# pcb-bldc-servo-3.net
KiCad netlist of a schematic drawn in EAGLE
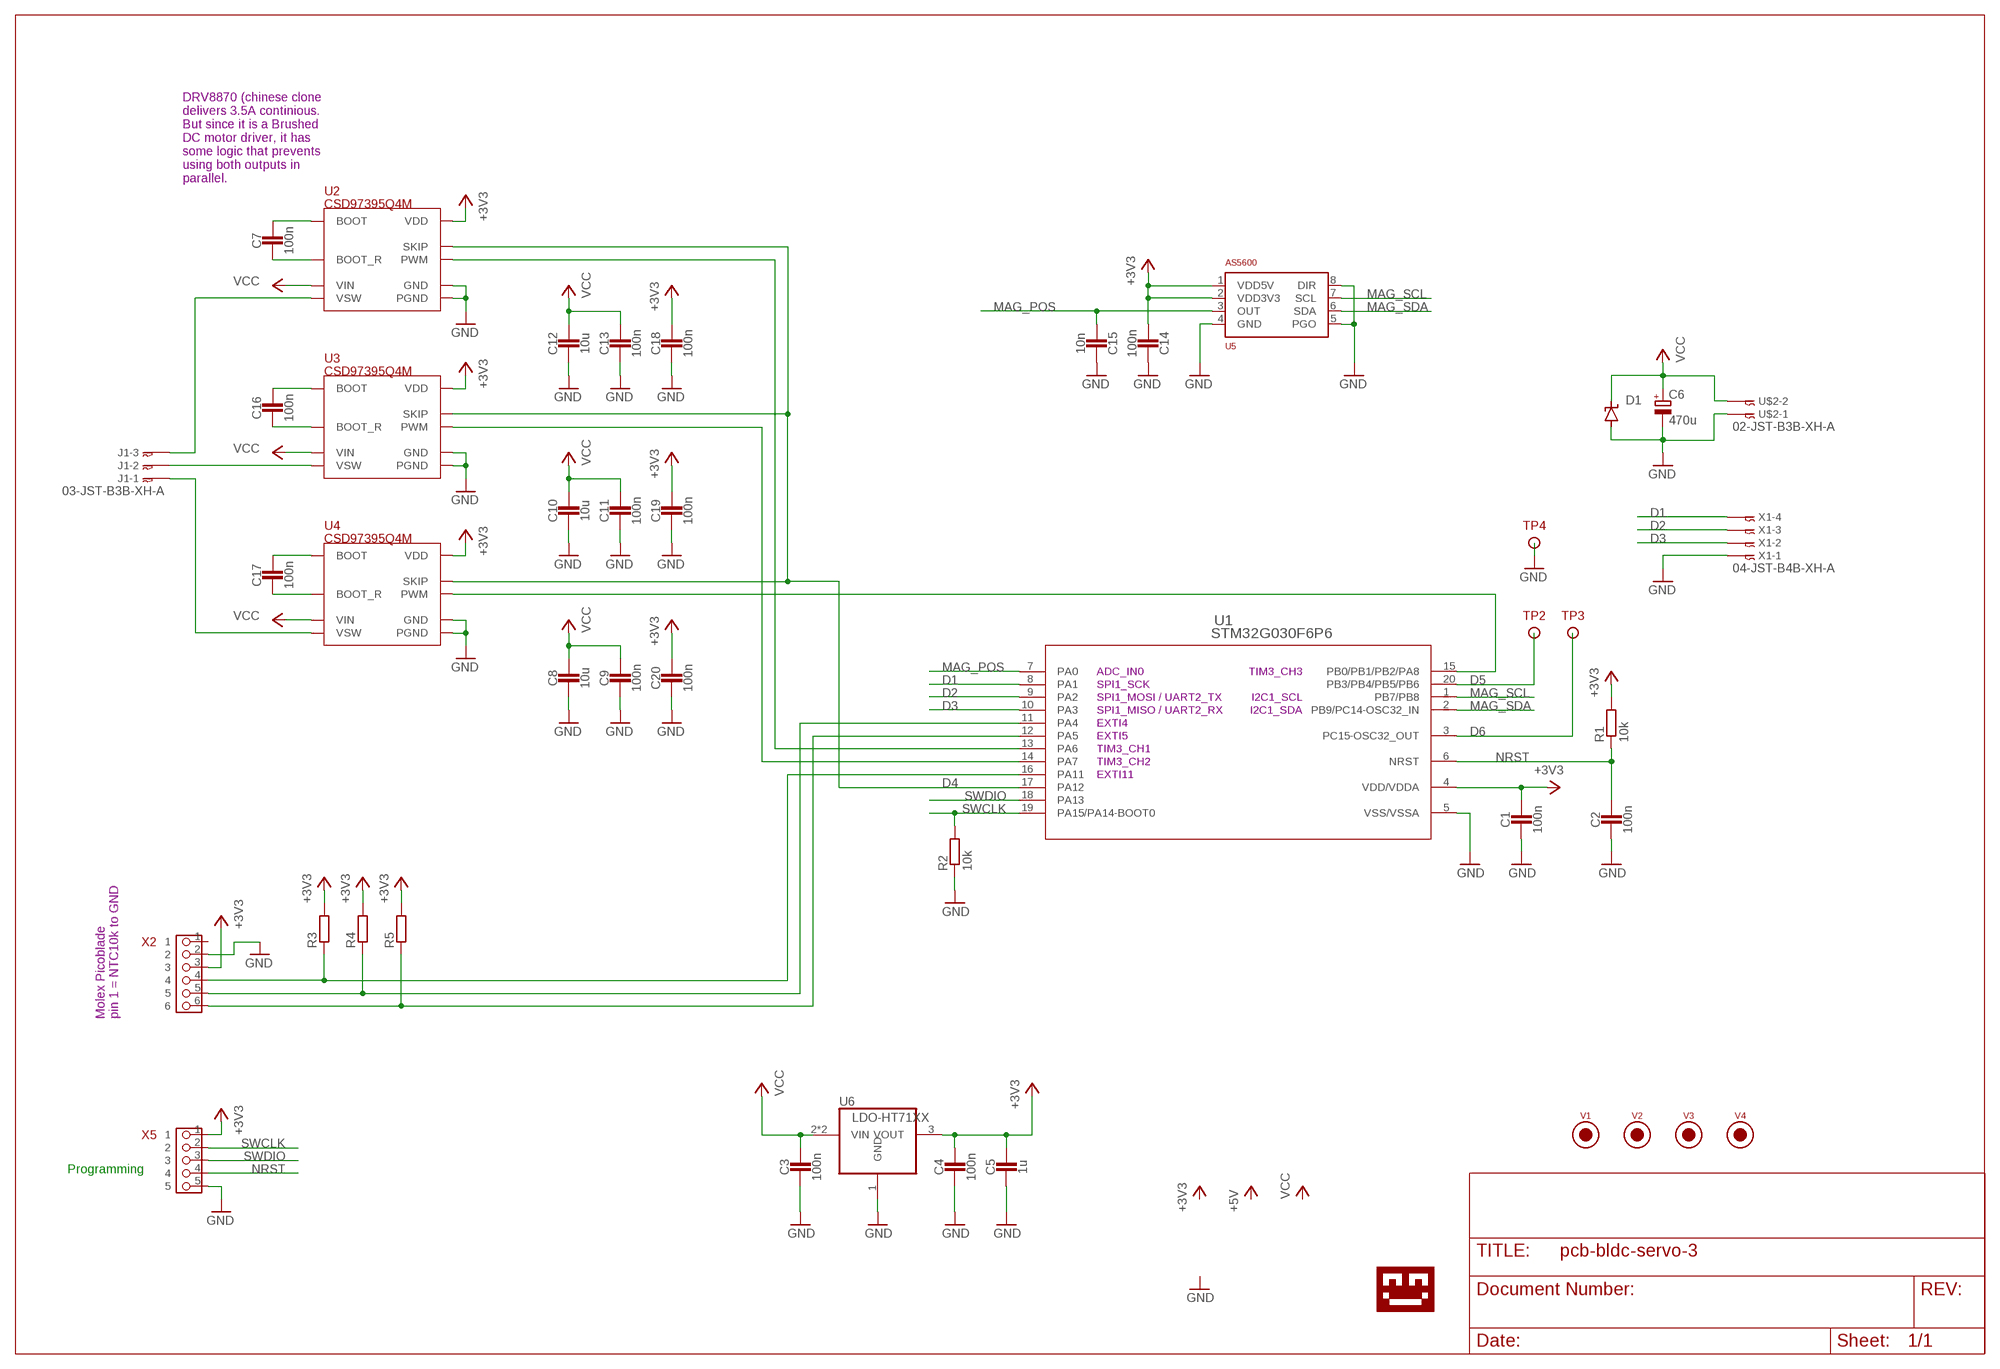
[diagram p0: schematic, sheet 1]

(export (version "E")
  (design (tool "Eeschema 10.0.6"))
  (components
    (comp (ref "C1")
      (value "100n")
      (footprint "eagle-import:0603_CAP")
      (libsource (lib "eagle-import") (part "CAPACITOR0603_CAP"))
    )
    (comp (ref "C2")
      (value "100n")
      (footprint "eagle-import:0603_CAP")
      (libsource (lib "eagle-import") (part "CAPACITOR0603_CAP"))
    )
    (comp (ref "C3")
      (value "100n")
      (footprint "eagle-import:0603_CAP")
      (libsource (lib "eagle-import") (part "CAPACITOR0603_CAP"))
    )
    (comp (ref "C4")
      (value "100n")
      (footprint "eagle-import:0603_CAP")
      (libsource (lib "eagle-import") (part "CAPACITOR0603_CAP"))
    )
    (comp (ref "C5")
      (value "1u")
      (footprint "eagle-import:0603_CAP")
      (libsource (lib "eagle-import") (part "CAPACITOR0603_CAP"))
    )
    (comp (ref "C6")
      (value "470u")
      (footprint "eagle-import:153CLV-1010")
      (libsource (lib "eagle-import") (part "CPOL-EU153CLV-1010"))
    )
    (comp (ref "C7")
      (value "100n")
      (footprint "eagle-import:0603_CAP")
      (libsource (lib "eagle-import") (part "CAPACITOR0603_CAP"))
    )
    (comp (ref "C8")
      (value "10u")
      (footprint "eagle-import:1206_CAP")
      (libsource (lib "eagle-import") (part "CAPACITOR1206_CAP"))
    )
    (comp (ref "C9")
      (value "100n")
      (footprint "eagle-import:0603_CAP")
      (libsource (lib "eagle-import") (part "CAPACITOR0603_CAP"))
    )
    (comp (ref "C10")
      (value "10u")
      (footprint "eagle-import:1206_CAP")
      (libsource (lib "eagle-import") (part "CAPACITOR1206_CAP"))
    )
    (comp (ref "C11")
      (value "100n")
      (footprint "eagle-import:0603_CAP")
      (libsource (lib "eagle-import") (part "CAPACITOR0603_CAP"))
    )
    (comp (ref "C12")
      (value "10u")
      (footprint "eagle-import:1206_CAP")
      (libsource (lib "eagle-import") (part "CAPACITOR1206_CAP"))
    )
    (comp (ref "C13")
      (value "100n")
      (footprint "eagle-import:0603_CAP")
      (libsource (lib "eagle-import") (part "CAPACITOR0603_CAP"))
    )
    (comp (ref "C14")
      (value "100n")
      (footprint "eagle-import:0603_CAP")
      (libsource (lib "eagle-import") (part "CAPACITOR0603_CAP"))
    )
    (comp (ref "C15")
      (value "10n")
      (footprint "eagle-import:0603_CAP")
      (libsource (lib "eagle-import") (part "CAPACITOR0603_CAP"))
    )
    (comp (ref "C16")
      (value "100n")
      (footprint "eagle-import:0603_CAP")
      (libsource (lib "eagle-import") (part "CAPACITOR0603_CAP"))
    )
    (comp (ref "C17")
      (value "100n")
      (footprint "eagle-import:0603_CAP")
      (libsource (lib "eagle-import") (part "CAPACITOR0603_CAP"))
    )
    (comp (ref "C18")
      (value "100n")
      (footprint "eagle-import:0603_CAP")
      (libsource (lib "eagle-import") (part "CAPACITOR0603_CAP"))
    )
    (comp (ref "C19")
      (value "100n")
      (footprint "eagle-import:0603_CAP")
      (libsource (lib "eagle-import") (part "CAPACITOR0603_CAP"))
    )
    (comp (ref "C20")
      (value "100n")
      (footprint "eagle-import:0603_CAP")
      (libsource (lib "eagle-import") (part "CAPACITOR0603_CAP"))
    )
    (comp (ref "D1")
      (value "SUPPRESSOR-SMBJ")
      (footprint "eagle-import:SMBJ")
      (libsource (lib "eagle-import") (part "SUPPRESSOR-SMBJ"))
    )
    (comp (ref "J1")
      (value "03-JST-B3B-XH-A")
      (footprint "eagle-import:B3B-XH")
      (libsource (lib "eagle-import") (part "03-JST-B3B-XH-A"))
    )
    (comp (ref "R1")
      (value "10k")
      (footprint "eagle-import:0603-RES")
      (libsource (lib "eagle-import") (part "RESISTOR0603_RES"))
    )
    (comp (ref "R2")
      (value "10k")
      (footprint "eagle-import:0603-RES")
      (libsource (lib "eagle-import") (part "RESISTOR0603_RES"))
    )
    (comp (ref "R3")
      (value "RESISTOR0603_RES")
      (footprint "eagle-import:0603-RES")
      (libsource (lib "eagle-import") (part "RESISTOR0603_RES"))
    )
    (comp (ref "R4")
      (value "RESISTOR0603_RES")
      (footprint "eagle-import:0603-RES")
      (libsource (lib "eagle-import") (part "RESISTOR0603_RES"))
    )
    (comp (ref "R5")
      (value "RESISTOR0603_RES")
      (footprint "eagle-import:0603-RES")
      (libsource (lib "eagle-import") (part "RESISTOR0603_RES"))
    )
    (comp (ref "TP2")
      (value "TESTPIN1MM")
      (footprint "eagle-import:PIN-SMD-1X1-TEST_1M0")
      (libsource (lib "eagle-import") (part "TESTPIN1MM"))
    )
    (comp (ref "TP3")
      (value "TESTPIN1MM")
      (footprint "eagle-import:PIN-SMD-1X1-TEST_1M0")
      (libsource (lib "eagle-import") (part "TESTPIN1MM"))
    )
    (comp (ref "TP4")
      (value "TESTPIN1MM")
      (footprint "eagle-import:PIN-SMD-1X1-TEST_1M0")
      (libsource (lib "eagle-import") (part "TESTPIN1MM"))
    )
    (comp (ref "U$1")
      (value "LOGO-TOBENG-1MM-FINISH")
      (footprint "eagle-import:TOBENG-1MM-FINISH")
      (libsource (lib "eagle-import") (part "LOGO-TOBENG-1MM-FINISH"))
    )
    (comp (ref "U$2")
      (value "02-JST-B3B-XH-A")
      (footprint "eagle-import:B2B-XH")
      (libsource (lib "eagle-import") (part "02-JST-B3B-XH-A"))
    )
    (comp (ref "U1")
      (value "STM32G030F6P6")
      (footprint "eagle-import:TSSOP20")
      (fields (field (name "COPYRIGHT") "Copyright (C) 2024 Ultra Librarian. All rights reserved."))
      (libsource (lib "eagle-import") (part "STM32G030F6P6"))
    )
    (comp (ref "U2")
      (value "CSD97395Q4M")
      (footprint "eagle-import:CSD97395Q4M")
      (libsource (lib "eagle-import") (part "CSD97395Q4M"))
    )
    (comp (ref "U3")
      (value "CSD97395Q4M")
      (footprint "eagle-import:CSD97395Q4M")
      (libsource (lib "eagle-import") (part "CSD97395Q4M"))
    )
    (comp (ref "U4")
      (value "CSD97395Q4M")
      (footprint "eagle-import:CSD97395Q4M")
      (libsource (lib "eagle-import") (part "CSD97395Q4M"))
    )
    (comp (ref "U5")
      (value "AS5600")
      (footprint "eagle-import:SOIC-8")
      (libsource (lib "eagle-import") (part "AS5600"))
    )
    (comp (ref "U6")
      (value "LDO-HT71XX")
      (footprint "eagle-import:SOT-89")
      (libsource (lib "eagle-import") (part "LDO-HT71XX"))
    )
    (comp (ref "V1")
      (value "FIDUCIAL2MM")
      (footprint "eagle-import:FIDUCIAL_2MM")
      (libsource (lib "eagle-import") (part "FIDUCIAL2MM"))
    )
    (comp (ref "V2")
      (value "FIDUCIAL2MM")
      (footprint "eagle-import:FIDUCIAL_2MM")
      (libsource (lib "eagle-import") (part "FIDUCIAL2MM"))
    )
    (comp (ref "V3")
      (value "FIDUCIAL2MM")
      (footprint "eagle-import:FIDUCIAL_2MM")
      (libsource (lib "eagle-import") (part "FIDUCIAL2MM"))
    )
    (comp (ref "V4")
      (value "FIDUCIAL2MM")
      (footprint "eagle-import:FIDUCIAL_2MM")
      (libsource (lib "eagle-import") (part "FIDUCIAL2MM"))
    )
    (comp (ref "X1")
      (value "04-JST-B4B-XH-A")
      (footprint "eagle-import:B4B-XH")
      (libsource (lib "eagle-import") (part "04-JST-B4B-XH-A"))
    )
    (comp (ref "X2")
      (value "PIN_6X1")
      (footprint "eagle-import:PIN_6X1_MOLEX_PICOBLADE")
      (libsource (lib "eagle-import") (part "PIN_6X1"))
    )
    (comp (ref "X5")
      (value "PIN_5X1HD")
      (footprint "eagle-import:PIN_5X1_HD")
      (libsource (lib "eagle-import") (part "PIN_5X1HD"))
    )
  )
  (nets
    (net (code "1") (name "+3V3") (class "Default")
      (node (ref "C1") (pin "1") (pinfunction "1_1") (pintype "bidirectional"))
      (node (ref "C14") (pin "1") (pinfunction "1_1") (pintype "bidirectional"))
      (node (ref "C18") (pin "1") (pinfunction "1_1") (pintype "bidirectional"))
      (node (ref "C19") (pin "1") (pinfunction "1_1") (pintype "bidirectional"))
      (node (ref "C20") (pin "1") (pinfunction "1_1") (pintype "bidirectional"))
      (node (ref "C4") (pin "1") (pinfunction "1_1") (pintype "bidirectional"))
      (node (ref "C5") (pin "1") (pinfunction "1_1") (pintype "bidirectional"))
      (node (ref "R1") (pin "2") (pinfunction "2_2") (pintype "passive"))
      (node (ref "R3") (pin "2") (pinfunction "2_2") (pintype "passive"))
      (node (ref "R4") (pin "2") (pinfunction "2_2") (pintype "passive"))
      (node (ref "R5") (pin "2") (pinfunction "2_2") (pintype "passive"))
      (node (ref "U1") (pin "4") (pinfunction "VDD/VDDA_4") (pintype "power_in"))
      (node (ref "U2") (pin "VDD") (pinfunction "VDD_VDD") (pintype "bidirectional"))
      (node (ref "U2") (pin "VDD1") (pinfunction "VDD_VDD1") (pintype "bidirectional"))
      (node (ref "U3") (pin "VDD") (pinfunction "VDD_VDD") (pintype "bidirectional"))
      (node (ref "U3") (pin "VDD1") (pinfunction "VDD_VDD1") (pintype "bidirectional"))
      (node (ref "U4") (pin "VDD") (pinfunction "VDD_VDD") (pintype "bidirectional"))
      (node (ref "U4") (pin "VDD1") (pinfunction "VDD_VDD1") (pintype "bidirectional"))
      (node (ref "U5") (pin "1") (pinfunction "VDD5V_1") (pintype "bidirectional"))
      (node (ref "U5") (pin "2") (pinfunction "VDD3V3_2") (pintype "bidirectional"))
      (node (ref "U6") (pin "3") (pinfunction "VOUT_3") (pintype "output"))
      (node (ref "X2") (pin "3") (pinfunction "3_3") (pintype "bidirectional"))
      (node (ref "X5") (pin "1") (pinfunction "1_1") (pintype "bidirectional"))
    )
    (net (code "3") (name "/D1") (class "Default")
      (node (ref "U1") (pin "8") (pinfunction "PA1_8") (pintype "bidirectional"))
      (node (ref "X1") (pin "P$4") (pinfunction "1_P$4") (pintype "passive"))
    )
    (net (code "4") (name "/D2") (class "Default")
      (node (ref "U1") (pin "9") (pinfunction "PA2_9") (pintype "bidirectional"))
      (node (ref "X1") (pin "P$3") (pinfunction "1_P$3") (pintype "passive"))
    )
    (net (code "5") (name "/D3") (class "Default")
      (node (ref "U1") (pin "10") (pinfunction "PA3_10") (pintype "bidirectional"))
      (node (ref "X1") (pin "P$2") (pinfunction "1_P$2") (pintype "passive"))
    )
    (net (code "6") (name "/D4") (class "Default")
      (node (ref "U1") (pin "17") (pinfunction "PA12_17") (pintype "bidirectional"))
      (node (ref "U2") (pin "SKIP") (pinfunction "SKIP_SKIP") (pintype "bidirectional"))
      (node (ref "U2") (pin "SKIP1") (pinfunction "SKIP_SKIP1") (pintype "bidirectional"))
      (node (ref "U3") (pin "SKIP") (pinfunction "SKIP_SKIP") (pintype "bidirectional"))
      (node (ref "U3") (pin "SKIP1") (pinfunction "SKIP_SKIP1") (pintype "bidirectional"))
      (node (ref "U4") (pin "SKIP") (pinfunction "SKIP_SKIP") (pintype "bidirectional"))
      (node (ref "U4") (pin "SKIP1") (pinfunction "SKIP_SKIP1") (pintype "bidirectional"))
    )
    (net (code "7") (name "/D5") (class "Default")
      (node (ref "TP2") (pin "1") (pinfunction "1_1") (pintype "bidirectional"))
      (node (ref "U1") (pin "20") (pinfunction "PB3/PB4/PB5/PB6_20") (pintype "bidirectional"))
    )
    (net (code "8") (name "/D6") (class "Default")
      (node (ref "TP3") (pin "1") (pinfunction "1_1") (pintype "bidirectional"))
      (node (ref "U1") (pin "3") (pinfunction "PC15-OSC32_OUT_3") (pintype "bidirectional"))
    )
    (net (code "9") (name "/MAG_POS") (class "Default")
      (node (ref "C15") (pin "1") (pinfunction "1_1") (pintype "bidirectional"))
      (node (ref "U1") (pin "7") (pinfunction "PA0_7") (pintype "bidirectional"))
      (node (ref "U5") (pin "3") (pinfunction "OUT_3") (pintype "bidirectional"))
    )
    (net (code "10") (name "/MAG_SCL") (class "Default")
      (node (ref "U1") (pin "1") (pinfunction "PB7/PB8_1") (pintype "bidirectional"))
      (node (ref "U5") (pin "7") (pinfunction "SCL_7") (pintype "bidirectional"))
    )
    (net (code "11") (name "/MAG_SDA") (class "Default")
      (node (ref "U1") (pin "2") (pinfunction "PB9/PC14-OSC32_IN_2") (pintype "bidirectional"))
      (node (ref "U5") (pin "6") (pinfunction "SDA_6") (pintype "bidirectional"))
    )
    (net (code "12") (name "/NRST") (class "Default")
      (node (ref "C2") (pin "1") (pinfunction "1_1") (pintype "bidirectional"))
      (node (ref "R1") (pin "1") (pinfunction "1_1") (pintype "passive"))
      (node (ref "U1") (pin "6") (pinfunction "NRST_6") (pintype "bidirectional"))
      (node (ref "X5") (pin "4") (pinfunction "4_4") (pintype "bidirectional"))
    )
    (net (code "13") (name "/SWCLK") (class "Default")
      (node (ref "R2") (pin "2") (pinfunction "2_2") (pintype "passive"))
      (node (ref "U1") (pin "19") (pinfunction "PA15/PA14-BOOT0_19") (pintype "bidirectional"))
      (node (ref "X5") (pin "2") (pinfunction "2_2") (pintype "bidirectional"))
    )
    (net (code "14") (name "/SWDIO") (class "Default")
      (node (ref "U1") (pin "18") (pinfunction "PA13_18") (pintype "bidirectional"))
      (node (ref "X5") (pin "3") (pinfunction "3_3") (pintype "bidirectional"))
    )
    (net (code "15") (name "GND") (class "Default")
      (node (ref "C1") (pin "2") (pinfunction "2_2") (pintype "bidirectional"))
      (node (ref "C10") (pin "2") (pinfunction "2_2") (pintype "bidirectional"))
      (node (ref "C11") (pin "2") (pinfunction "2_2") (pintype "bidirectional"))
      (node (ref "C12") (pin "2") (pinfunction "2_2") (pintype "bidirectional"))
      (node (ref "C13") (pin "2") (pinfunction "2_2") (pintype "bidirectional"))
      (node (ref "C14") (pin "2") (pinfunction "2_2") (pintype "bidirectional"))
      (node (ref "C15") (pin "2") (pinfunction "2_2") (pintype "bidirectional"))
      (node (ref "C18") (pin "2") (pinfunction "2_2") (pintype "bidirectional"))
      (node (ref "C19") (pin "2") (pinfunction "2_2") (pintype "bidirectional"))
      (node (ref "C2") (pin "2") (pinfunction "2_2") (pintype "bidirectional"))
      (node (ref "C20") (pin "2") (pinfunction "2_2") (pintype "bidirectional"))
      (node (ref "C3") (pin "2") (pinfunction "2_2") (pintype "bidirectional"))
      (node (ref "C4") (pin "2") (pinfunction "2_2") (pintype "bidirectional"))
      (node (ref "C5") (pin "2") (pinfunction "2_2") (pintype "bidirectional"))
      (node (ref "C6") (pin "-") (pinfunction "-_-") (pintype "passive"))
      (node (ref "C8") (pin "2") (pinfunction "2_2") (pintype "bidirectional"))
      (node (ref "C9") (pin "2") (pinfunction "2_2") (pintype "bidirectional"))
      (node (ref "D1") (pin "A") (pinfunction "A_A") (pintype "passive"))
      (node (ref "R2") (pin "1") (pinfunction "1_1") (pintype "passive"))
      (node (ref "TP4") (pin "1") (pinfunction "1_1") (pintype "bidirectional"))
      (node (ref "U$2") (pin "P$1") (pinfunction "1_P$1") (pintype "passive"))
      (node (ref "U1") (pin "5") (pinfunction "VSS/VSSA_5") (pintype "power_in"))
      (node (ref "U2") (pin "GND") (pinfunction "GND_GND") (pintype "bidirectional"))
      (node (ref "U2") (pin "GND1") (pinfunction "GND_GND1") (pintype "bidirectional"))
      (node (ref "U2") (pin "PGND") (pinfunction "PGND_PGND") (pintype "bidirectional"))
      (node (ref "U3") (pin "GND") (pinfunction "GND_GND") (pintype "bidirectional"))
      (node (ref "U3") (pin "GND1") (pinfunction "GND_GND1") (pintype "bidirectional"))
      (node (ref "U3") (pin "PGND") (pinfunction "PGND_PGND") (pintype "bidirectional"))
      (node (ref "U4") (pin "GND") (pinfunction "GND_GND") (pintype "bidirectional"))
      (node (ref "U4") (pin "GND1") (pinfunction "GND_GND1") (pintype "bidirectional"))
      (node (ref "U4") (pin "PGND") (pinfunction "PGND_PGND") (pintype "bidirectional"))
      (node (ref "U5") (pin "4") (pinfunction "GND_4") (pintype "bidirectional"))
      (node (ref "U5") (pin "5") (pinfunction "PGO_5") (pintype "bidirectional"))
      (node (ref "U5") (pin "8") (pinfunction "DIR_8") (pintype "bidirectional"))
      (node (ref "U6") (pin "1") (pinfunction "GND_1") (pintype "power_in"))
      (node (ref "X1") (pin "P$1") (pinfunction "1_P$1") (pintype "passive"))
      (node (ref "X2") (pin "2") (pinfunction "2_2") (pintype "bidirectional"))
      (node (ref "X5") (pin "5") (pinfunction "5_5") (pintype "bidirectional"))
    )
    (net (code "16") (name "Net-(C7-Pad1)") (class "Default")
      (node (ref "C7") (pin "1") (pinfunction "1_1") (pintype "bidirectional"))
      (node (ref "U2") (pin "BOOT") (pinfunction "BOOT_BOOT") (pintype "bidirectional"))
      (node (ref "U2") (pin "BOOT1") (pinfunction "BOOT_BOOT1") (pintype "bidirectional"))
    )
    (net (code "17") (name "Net-(C7-Pad2)") (class "Default")
      (node (ref "C7") (pin "2") (pinfunction "2_2") (pintype "bidirectional"))
      (node (ref "U2") (pin "BOOT_R") (pinfunction "BOOT_R_BOOT_R") (pintype "bidirectional"))
      (node (ref "U2") (pin "BOOT_R1") (pinfunction "BOOT_R_BOOT_R1") (pintype "bidirectional"))
    )
    (net (code "18") (name "Net-(C16-Pad1)") (class "Default")
      (node (ref "C16") (pin "1") (pinfunction "1_1") (pintype "bidirectional"))
      (node (ref "U3") (pin "BOOT") (pinfunction "BOOT_BOOT") (pintype "bidirectional"))
      (node (ref "U3") (pin "BOOT1") (pinfunction "BOOT_BOOT1") (pintype "bidirectional"))
    )
    (net (code "19") (name "Net-(C16-Pad2)") (class "Default")
      (node (ref "C16") (pin "2") (pinfunction "2_2") (pintype "bidirectional"))
      (node (ref "U3") (pin "BOOT_R") (pinfunction "BOOT_R_BOOT_R") (pintype "bidirectional"))
      (node (ref "U3") (pin "BOOT_R1") (pinfunction "BOOT_R_BOOT_R1") (pintype "bidirectional"))
    )
    (net (code "20") (name "Net-(C17-Pad1)") (class "Default")
      (node (ref "C17") (pin "1") (pinfunction "1_1") (pintype "bidirectional"))
      (node (ref "U4") (pin "BOOT") (pinfunction "BOOT_BOOT") (pintype "bidirectional"))
      (node (ref "U4") (pin "BOOT1") (pinfunction "BOOT_BOOT1") (pintype "bidirectional"))
    )
    (net (code "21") (name "Net-(C17-Pad2)") (class "Default")
      (node (ref "C17") (pin "2") (pinfunction "2_2") (pintype "bidirectional"))
      (node (ref "U4") (pin "BOOT_R") (pinfunction "BOOT_R_BOOT_R") (pintype "bidirectional"))
      (node (ref "U4") (pin "BOOT_R1") (pinfunction "BOOT_R_BOOT_R1") (pintype "bidirectional"))
    )
    (net (code "22") (name "Net-(J1A-1)") (class "Default")
      (node (ref "J1") (pin "P$1") (pinfunction "1_P$1") (pintype "passive"))
      (node (ref "U4") (pin "VSW") (pinfunction "VSW_VSW") (pintype "bidirectional"))
      (node (ref "U4") (pin "VSW1") (pinfunction "VSW_VSW1") (pintype "bidirectional"))
      (node (ref "U4") (pin "VSW2") (pinfunction "VSW_VSW2") (pintype "bidirectional"))
      (node (ref "U4") (pin "VSW3") (pinfunction "VSW_VSW3") (pintype "bidirectional"))
      (node (ref "U4") (pin "VSW4") (pinfunction "VSW_VSW4") (pintype "bidirectional"))
      (node (ref "U4") (pin "VSW5") (pinfunction "VSW_VSW5") (pintype "bidirectional"))
      (node (ref "U4") (pin "VSW6") (pinfunction "VSW_VSW6") (pintype "bidirectional"))
    )
    (net (code "23") (name "Net-(J1B-1)") (class "Default")
      (node (ref "J1") (pin "P$2") (pinfunction "1_P$2") (pintype "passive"))
      (node (ref "U3") (pin "VSW") (pinfunction "VSW_VSW") (pintype "bidirectional"))
      (node (ref "U3") (pin "VSW1") (pinfunction "VSW_VSW1") (pintype "bidirectional"))
      (node (ref "U3") (pin "VSW2") (pinfunction "VSW_VSW2") (pintype "bidirectional"))
      (node (ref "U3") (pin "VSW3") (pinfunction "VSW_VSW3") (pintype "bidirectional"))
      (node (ref "U3") (pin "VSW4") (pinfunction "VSW_VSW4") (pintype "bidirectional"))
      (node (ref "U3") (pin "VSW5") (pinfunction "VSW_VSW5") (pintype "bidirectional"))
      (node (ref "U3") (pin "VSW6") (pinfunction "VSW_VSW6") (pintype "bidirectional"))
    )
    (net (code "24") (name "Net-(J1C-1)") (class "Default")
      (node (ref "J1") (pin "P$3") (pinfunction "1_P$3") (pintype "passive"))
      (node (ref "U2") (pin "VSW") (pinfunction "VSW_VSW") (pintype "bidirectional"))
      (node (ref "U2") (pin "VSW1") (pinfunction "VSW_VSW1") (pintype "bidirectional"))
      (node (ref "U2") (pin "VSW2") (pinfunction "VSW_VSW2") (pintype "bidirectional"))
      (node (ref "U2") (pin "VSW3") (pinfunction "VSW_VSW3") (pintype "bidirectional"))
      (node (ref "U2") (pin "VSW4") (pinfunction "VSW_VSW4") (pintype "bidirectional"))
      (node (ref "U2") (pin "VSW5") (pinfunction "VSW_VSW5") (pintype "bidirectional"))
      (node (ref "U2") (pin "VSW6") (pinfunction "VSW_VSW6") (pintype "bidirectional"))
    )
    (net (code "25") (name "Net-(U1-PA4)") (class "Default")
      (node (ref "R4") (pin "1") (pinfunction "1_1") (pintype "passive"))
      (node (ref "U1") (pin "11") (pinfunction "PA4_11") (pintype "bidirectional"))
      (node (ref "X2") (pin "5") (pinfunction "5_5") (pintype "bidirectional"))
    )
    (net (code "26") (name "Net-(U1-PA5)") (class "Default")
      (node (ref "R5") (pin "1") (pinfunction "1_1") (pintype "passive"))
      (node (ref "U1") (pin "12") (pinfunction "PA5_12") (pintype "bidirectional"))
      (node (ref "X2") (pin "6") (pinfunction "6_6") (pintype "bidirectional"))
    )
    (net (code "27") (name "Net-(U1-PA6)") (class "Default")
      (node (ref "U1") (pin "13") (pinfunction "PA6_13") (pintype "bidirectional"))
      (node (ref "U2") (pin "PWM") (pinfunction "PWM_PWM") (pintype "bidirectional"))
      (node (ref "U2") (pin "PWM1") (pinfunction "PWM_PWM1") (pintype "bidirectional"))
    )
    (net (code "28") (name "Net-(U1-PA7)") (class "Default")
      (node (ref "U1") (pin "14") (pinfunction "PA7_14") (pintype "bidirectional"))
      (node (ref "U3") (pin "PWM") (pinfunction "PWM_PWM") (pintype "bidirectional"))
      (node (ref "U3") (pin "PWM1") (pinfunction "PWM_PWM1") (pintype "bidirectional"))
    )
    (net (code "29") (name "Net-(U1-PA11)") (class "Default")
      (node (ref "R3") (pin "1") (pinfunction "1_1") (pintype "passive"))
      (node (ref "U1") (pin "16") (pinfunction "PA11_16") (pintype "bidirectional"))
      (node (ref "X2") (pin "4") (pinfunction "4_4") (pintype "bidirectional"))
    )
    (net (code "30") (name "Net-(U1-PB0{slash}PB1{slash}PB2{slash}PA8)") (class "Default")
      (node (ref "U1") (pin "15") (pinfunction "PB0/PB1/PB2/PA8_15") (pintype "bidirectional"))
      (node (ref "U4") (pin "PWM") (pinfunction "PWM_PWM") (pintype "bidirectional"))
      (node (ref "U4") (pin "PWM1") (pinfunction "PWM_PWM1") (pintype "bidirectional"))
    )
    (net (code "31") (name "VCC") (class "Default")
      (node (ref "C10") (pin "1") (pinfunction "1_1") (pintype "bidirectional"))
      (node (ref "C11") (pin "1") (pinfunction "1_1") (pintype "bidirectional"))
      (node (ref "C12") (pin "1") (pinfunction "1_1") (pintype "bidirectional"))
      (node (ref "C13") (pin "1") (pinfunction "1_1") (pintype "bidirectional"))
      (node (ref "C3") (pin "1") (pinfunction "1_1") (pintype "bidirectional"))
      (node (ref "C6") (pin "+") (pinfunction "+_+") (pintype "passive"))
      (node (ref "C8") (pin "1") (pinfunction "1_1") (pintype "bidirectional"))
      (node (ref "C9") (pin "1") (pinfunction "1_1") (pintype "bidirectional"))
      (node (ref "D1") (pin "C") (pinfunction "C_C") (pintype "passive"))
      (node (ref "U$2") (pin "P$2") (pinfunction "1_P$2") (pintype "passive"))
      (node (ref "U2") (pin "VIN") (pinfunction "VIN_VIN") (pintype "bidirectional"))
      (node (ref "U2") (pin "VIN1") (pinfunction "VIN_VIN1") (pintype "bidirectional"))
      (node (ref "U2") (pin "VIN2") (pinfunction "VIN_VIN2") (pintype "bidirectional"))
      (node (ref "U2") (pin "VIN3") (pinfunction "VIN_VIN3") (pintype "bidirectional"))
      (node (ref "U2") (pin "VIN4") (pinfunction "VIN_VIN4") (pintype "bidirectional"))
      (node (ref "U2") (pin "VIN5") (pinfunction "VIN_VIN5") (pintype "bidirectional"))
      (node (ref "U2") (pin "VIN6") (pinfunction "VIN_VIN6") (pintype "bidirectional"))
      (node (ref "U3") (pin "VIN") (pinfunction "VIN_VIN") (pintype "bidirectional"))
      (node (ref "U3") (pin "VIN1") (pinfunction "VIN_VIN1") (pintype "bidirectional"))
      (node (ref "U3") (pin "VIN2") (pinfunction "VIN_VIN2") (pintype "bidirectional"))
      (node (ref "U3") (pin "VIN3") (pinfunction "VIN_VIN3") (pintype "bidirectional"))
      (node (ref "U3") (pin "VIN4") (pinfunction "VIN_VIN4") (pintype "bidirectional"))
      (node (ref "U3") (pin "VIN5") (pinfunction "VIN_VIN5") (pintype "bidirectional"))
      (node (ref "U3") (pin "VIN6") (pinfunction "VIN_VIN6") (pintype "bidirectional"))
      (node (ref "U4") (pin "VIN") (pinfunction "VIN_VIN") (pintype "bidirectional"))
      (node (ref "U4") (pin "VIN1") (pinfunction "VIN_VIN1") (pintype "bidirectional"))
      (node (ref "U4") (pin "VIN2") (pinfunction "VIN_VIN2") (pintype "bidirectional"))
      (node (ref "U4") (pin "VIN3") (pinfunction "VIN_VIN3") (pintype "bidirectional"))
      (node (ref "U4") (pin "VIN4") (pinfunction "VIN_VIN4") (pintype "bidirectional"))
      (node (ref "U4") (pin "VIN5") (pinfunction "VIN_VIN5") (pintype "bidirectional"))
      (node (ref "U4") (pin "VIN6") (pinfunction "VIN_VIN6") (pintype "bidirectional"))
      (node (ref "U6") (pin "2") (pinfunction "VIN_2") (pintype "input"))
      (node (ref "U6") (pin "2@1") (pinfunction "VIN_2@1") (pintype "input"))
    )
    (net (code "32") (name "unconnected-(X2-Pad1)") (class "Default")
      (node (ref "X2") (pin "1") (pinfunction "1_1") (pintype "bidirectional"))
    )
  )
)
